# 08_SAMA7G54-DDR3.net
KiCad netlist of a schematic drawn in Altium Designer
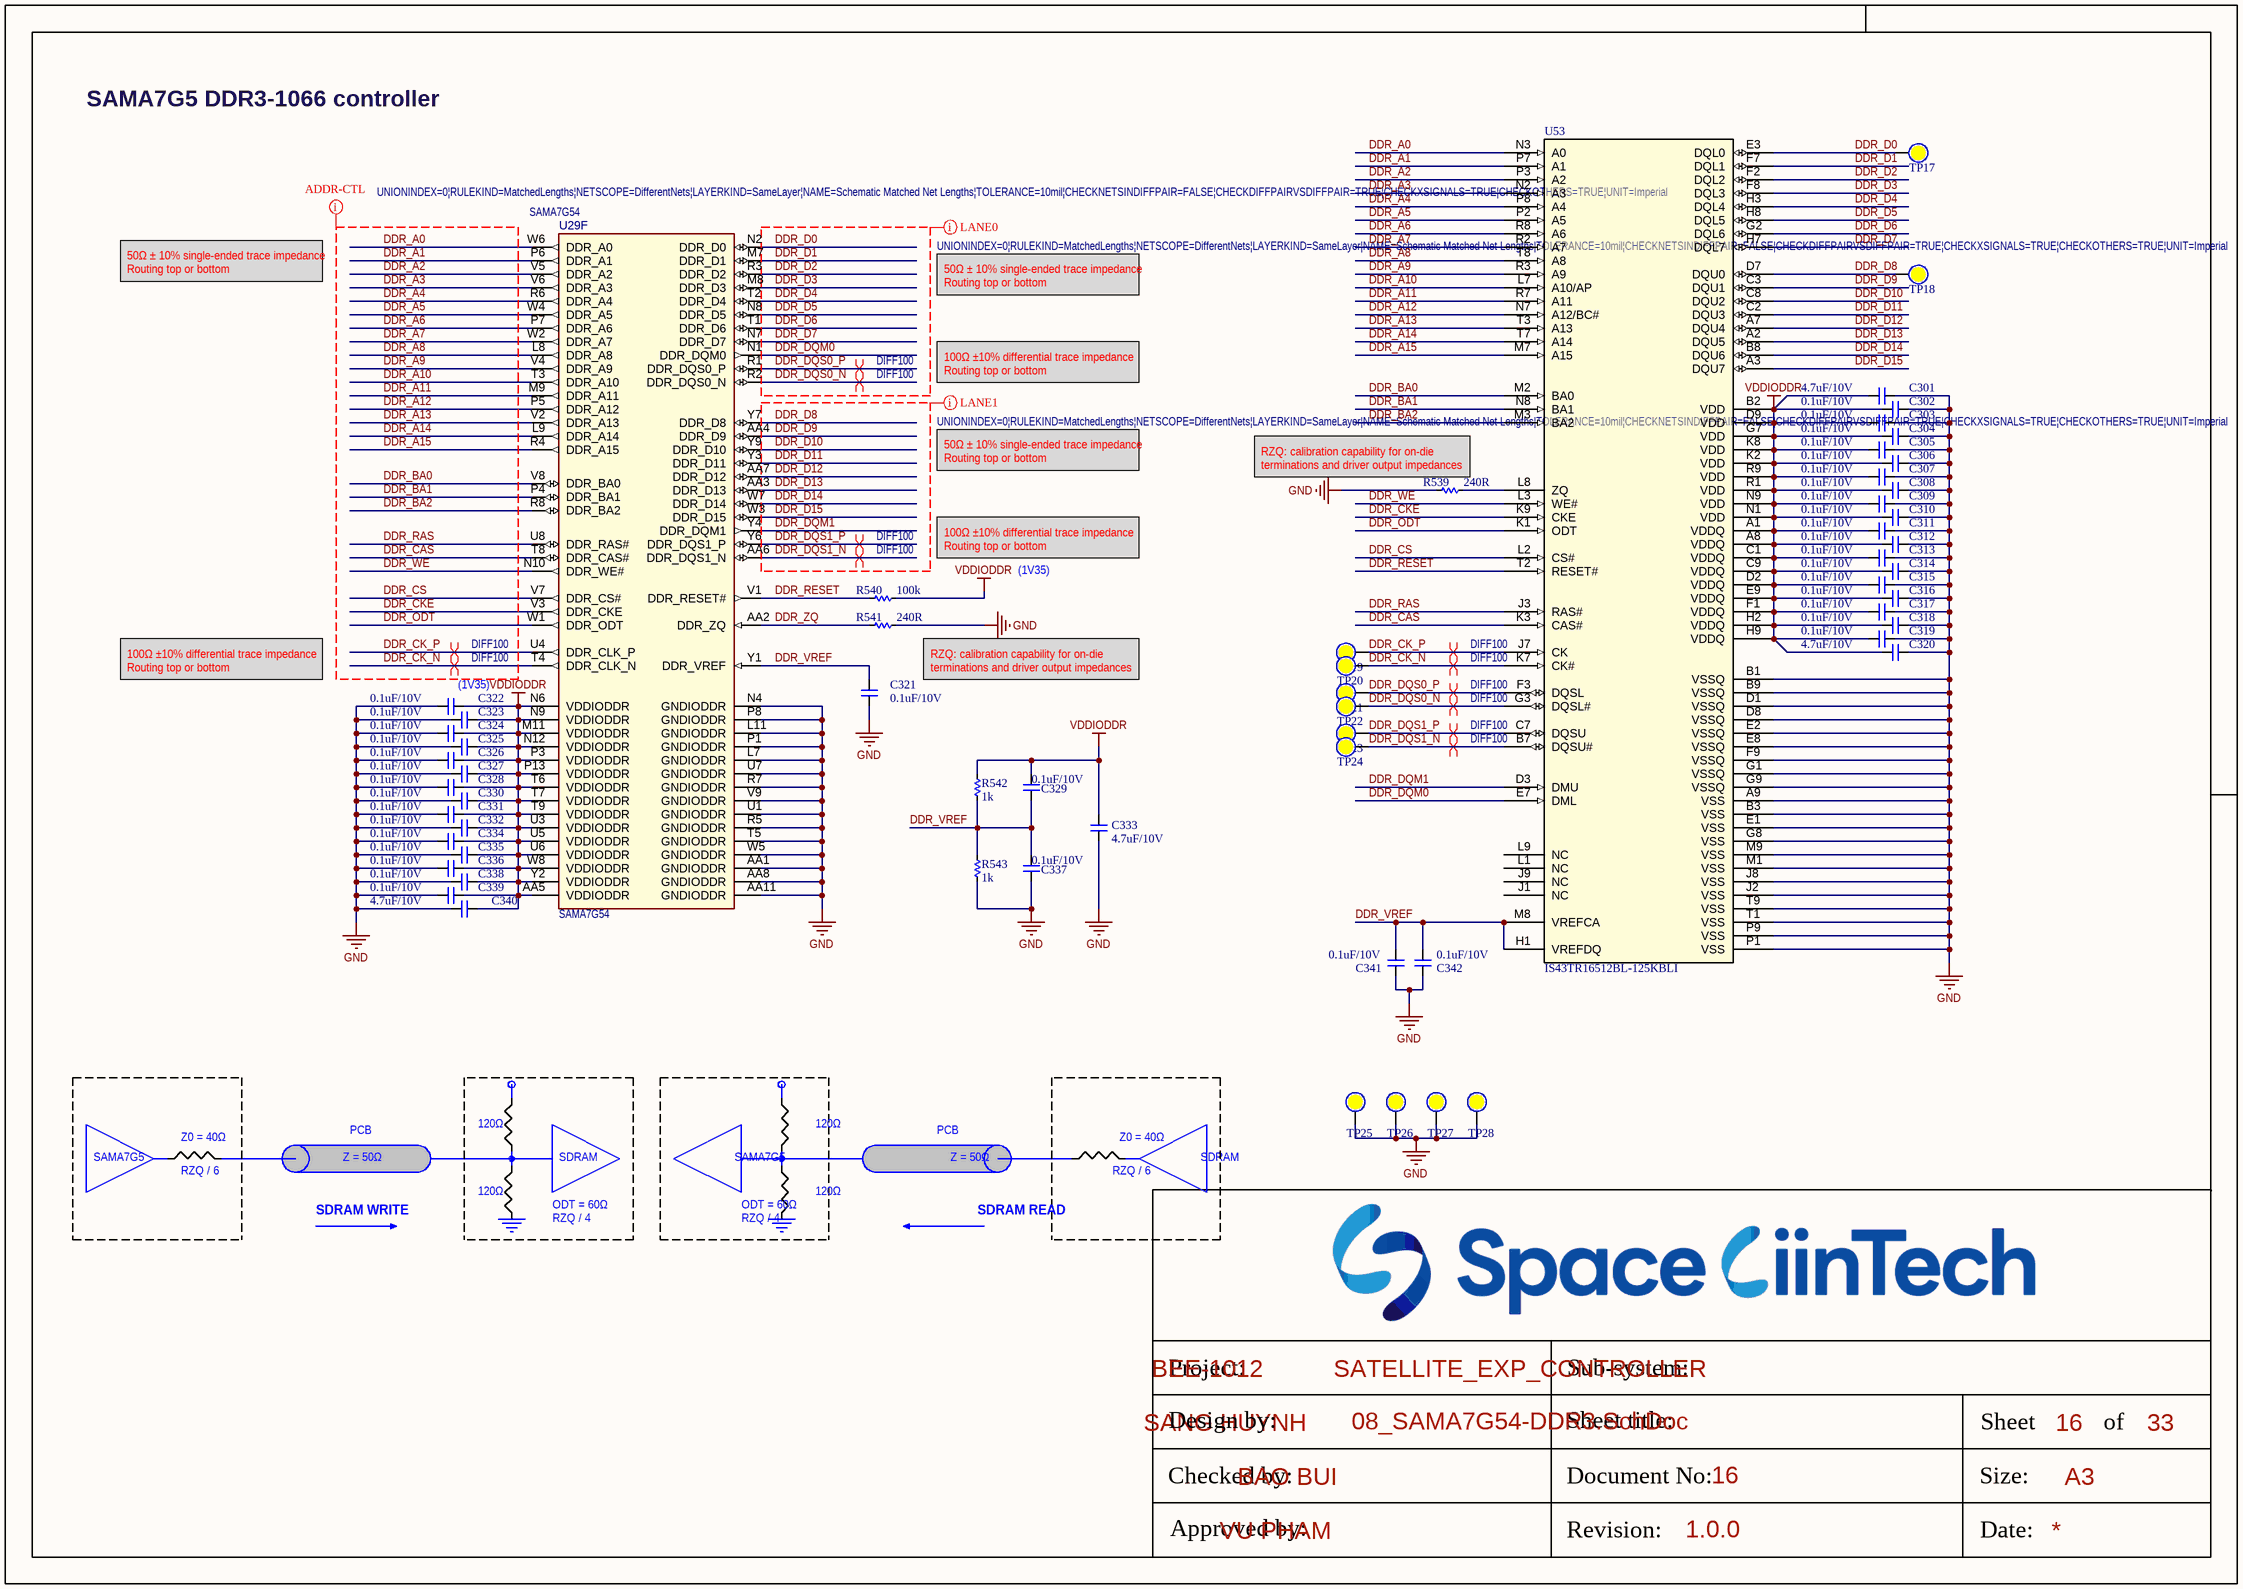
[diagram p0: 08_SAMA7G54-DDR3.SchDoc]

(export (version "E")
  (design (tool "Eeschema 10.0.6"))
  (components
    (comp (ref "C301")
      (value "4.7uF/10V")
      (footprint "CAP_C_1005X50_L")
      (description "CAP")
      (libsource (lib "LABLIB") (part "_CAP_C_2"))
    )
    (comp (ref "C302")
      (value "0.1uF/10V")
      (footprint "CAP_C_0603x30")
      (description "CAP")
      (libsource (lib "LABLIB") (part "_CAP_C_2"))
    )
    (comp (ref "C303")
      (value "0.1uF/10V")
      (footprint "CAP_C_0603x30")
      (description "CAP")
      (libsource (lib "LABLIB") (part "_CAP_C_2"))
    )
    (comp (ref "C304")
      (value "0.1uF/10V")
      (footprint "CAP_C_0603x30")
      (description "CAP")
      (libsource (lib "LABLIB") (part "_CAP_C_2"))
    )
    (comp (ref "C305")
      (value "0.1uF/10V")
      (footprint "CAP_C_0603x30")
      (description "CAP")
      (libsource (lib "LABLIB") (part "_CAP_C_2"))
    )
    (comp (ref "C306")
      (value "0.1uF/10V")
      (footprint "CAP_C_0603x30")
      (description "CAP")
      (libsource (lib "LABLIB") (part "_CAP_C_2"))
    )
    (comp (ref "C307")
      (value "0.1uF/10V")
      (footprint "CAP_C_0603x30")
      (description "CAP")
      (libsource (lib "LABLIB") (part "_CAP_C_2"))
    )
    (comp (ref "C308")
      (value "0.1uF/10V")
      (footprint "CAP_C_0603x30")
      (description "CAP")
      (libsource (lib "LABLIB") (part "_CAP_C_2"))
    )
    (comp (ref "C309")
      (value "0.1uF/10V")
      (footprint "CAP_C_0603x30")
      (description "CAP")
      (libsource (lib "LABLIB") (part "_CAP_C_2"))
    )
    (comp (ref "C310")
      (value "0.1uF/10V")
      (footprint "CAP_C_0603x30")
      (description "CAP")
      (libsource (lib "LABLIB") (part "_CAP_C_2"))
    )
    (comp (ref "C311")
      (value "0.1uF/10V")
      (footprint "CAP_C_0603x30")
      (description "CAP")
      (libsource (lib "LABLIB") (part "_CAP_C_2"))
    )
    (comp (ref "C312")
      (value "0.1uF/10V")
      (footprint "CAP_C_0603x30")
      (description "CAP")
      (libsource (lib "LABLIB") (part "_CAP_C_2"))
    )
    (comp (ref "C313")
      (value "0.1uF/10V")
      (footprint "CAP_C_0603x30")
      (description "CAP")
      (libsource (lib "LABLIB") (part "_CAP_C_2"))
    )
    (comp (ref "C314")
      (value "0.1uF/10V")
      (footprint "CAP_C_0603x30")
      (description "CAP")
      (libsource (lib "LABLIB") (part "_CAP_C_2"))
    )
    (comp (ref "C315")
      (value "0.1uF/10V")
      (footprint "CAP_C_0603x30")
      (description "CAP")
      (libsource (lib "LABLIB") (part "_CAP_C_2"))
    )
    (comp (ref "C316")
      (value "0.1uF/10V")
      (footprint "CAP_C_0603x30")
      (description "CAP")
      (libsource (lib "LABLIB") (part "_CAP_C_2"))
    )
    (comp (ref "C317")
      (value "0.1uF/10V")
      (footprint "CAP_C_0603x30")
      (description "CAP")
      (libsource (lib "LABLIB") (part "_CAP_C_2"))
    )
    (comp (ref "C318")
      (value "0.1uF/10V")
      (footprint "CAP_C_0603x30")
      (description "CAP")
      (libsource (lib "LABLIB") (part "_CAP_C_2"))
    )
    (comp (ref "C319")
      (value "0.1uF/10V")
      (footprint "CAP_C_0603x30")
      (description "CAP")
      (libsource (lib "LABLIB") (part "_CAP_C_2"))
    )
    (comp (ref "C320")
      (value "4.7uF/10V")
      (footprint "CAP_C_1005X50_L")
      (description "CAP")
      (libsource (lib "LABLIB") (part "_CAP_C_2"))
    )
    (comp (ref "C321")
      (value "0.1uF/10V")
      (footprint "CAP_C_0603x30")
      (description "CAP")
      (libsource (lib "LABLIB") (part "_CAP_C_2"))
    )
    (comp (ref "C322")
      (value "0.1uF/10V")
      (footprint "CAP_C_0603x30")
      (description "CAP")
      (libsource (lib "LABLIB") (part "_CAP_C_2"))
    )
    (comp (ref "C323")
      (value "0.1uF/10V")
      (footprint "CAP_C_0603x30")
      (description "CAP")
      (libsource (lib "LABLIB") (part "_CAP_C_2"))
    )
    (comp (ref "C324")
      (value "0.1uF/10V")
      (footprint "CAP_C_0603x30")
      (description "CAP")
      (libsource (lib "LABLIB") (part "_CAP_C_2"))
    )
    (comp (ref "C325")
      (value "0.1uF/10V")
      (footprint "CAP_C_0603x30")
      (description "CAP")
      (libsource (lib "LABLIB") (part "_CAP_C_2"))
    )
    (comp (ref "C326")
      (value "0.1uF/10V")
      (footprint "CAP_C_0603x30")
      (description "CAP")
      (libsource (lib "LABLIB") (part "_CAP_C_2"))
    )
    (comp (ref "C327")
      (value "0.1uF/10V")
      (footprint "CAP_C_0603x30")
      (description "CAP")
      (libsource (lib "LABLIB") (part "_CAP_C_2"))
    )
    (comp (ref "C328")
      (value "0.1uF/10V")
      (footprint "CAP_C_0603x30")
      (description "CAP")
      (libsource (lib "LABLIB") (part "_CAP_C_2"))
    )
    (comp (ref "C329")
      (value "0.1uF/10V")
      (footprint "CAP_C_0603x30")
      (description "CAP")
      (libsource (lib "LABLIB") (part "_CAP_C_2"))
    )
    (comp (ref "C330")
      (value "0.1uF/10V")
      (footprint "CAP_C_0603x30")
      (description "CAP")
      (libsource (lib "LABLIB") (part "_CAP_C_2"))
    )
    (comp (ref "C331")
      (value "0.1uF/10V")
      (footprint "CAP_C_0603x30")
      (description "CAP")
      (libsource (lib "LABLIB") (part "_CAP_C_2"))
    )
    (comp (ref "C332")
      (value "0.1uF/10V")
      (footprint "CAP_C_0603x30")
      (description "CAP")
      (libsource (lib "LABLIB") (part "_CAP_C_2"))
    )
    (comp (ref "C333")
      (value "4.7uF/10V")
      (footprint "CAP_C_1005X50_L")
      (description "CAP")
      (libsource (lib "LABLIB") (part "_CAP_C_2"))
    )
    (comp (ref "C334")
      (value "0.1uF/10V")
      (footprint "CAP_C_0603x30")
      (description "CAP")
      (libsource (lib "LABLIB") (part "_CAP_C_2"))
    )
    (comp (ref "C335")
      (value "0.1uF/10V")
      (footprint "CAP_C_0603x30")
      (description "CAP")
      (libsource (lib "LABLIB") (part "_CAP_C_2"))
    )
    (comp (ref "C336")
      (value "0.1uF/10V")
      (footprint "CAP_C_0603x30")
      (description "CAP")
      (libsource (lib "LABLIB") (part "_CAP_C_2"))
    )
    (comp (ref "C337")
      (value "0.1uF/10V")
      (footprint "CAP_C_0603x30")
      (description "CAP")
      (libsource (lib "LABLIB") (part "_CAP_C_2"))
    )
    (comp (ref "C338")
      (value "0.1uF/10V")
      (footprint "CAP_C_0603x30")
      (description "CAP")
      (libsource (lib "LABLIB") (part "_CAP_C_2"))
    )
    (comp (ref "C339")
      (value "0.1uF/10V")
      (footprint "CAP_C_0603x30")
      (description "CAP")
      (libsource (lib "LABLIB") (part "_CAP_C_2"))
    )
    (comp (ref "C340")
      (value "4.7uF/10V")
      (footprint "CAP_C_1005X50_L")
      (description "CAP")
      (libsource (lib "LABLIB") (part "_CAP_C_2"))
    )
    (comp (ref "C341")
      (value "0.1uF/10V")
      (footprint "CAP_C_0603x30")
      (description "CAP")
      (libsource (lib "LABLIB") (part "_CAP_C_2"))
    )
    (comp (ref "C342")
      (value "0.1uF/10V")
      (footprint "CAP_C_0603x30")
      (description "CAP")
      (libsource (lib "LABLIB") (part "_CAP_C_2"))
    )
    (comp (ref "R539")
      (value "240R")
      (footprint "RES_C_0603X30")
      (description "RES")
      (libsource (lib "LABLIB") (part "_RES_B_2"))
    )
    (comp (ref "R540")
      (value "100k")
      (footprint "RES_C_0603X30")
      (description "RES")
      (libsource (lib "LABLIB") (part "_RES_B_2"))
    )
    (comp (ref "R541")
      (value "240R")
      (footprint "RES_C_0603X30")
      (description "RES")
      (libsource (lib "LABLIB") (part "_RES_B_2"))
    )
    (comp (ref "R542")
      (value "1k")
      (footprint "RES_C_0603X30")
      (description "RES")
      (libsource (lib "LABLIB") (part "_RES_B_2"))
    )
    (comp (ref "R543")
      (value "1k")
      (footprint "RES_C_0603X30")
      (description "RES")
      (libsource (lib "LABLIB") (part "_RES_B_2"))
    )
    (comp (ref "TP17")
      (value "~")
      (footprint "TP_1mm_SMD")
      (description "Test Point")
      (libsource (lib "") (part "Test Point_2"))
    )
    (comp (ref "TP18")
      (value "~")
      (footprint "TP_1mm_SMD")
      (description "Test Point")
      (libsource (lib "") (part "Test Point_2"))
    )
    (comp (ref "TP19")
      (value "~")
      (footprint "TP_1mm_SMD")
      (description "Test Point")
      (libsource (lib "LABLIB") (part "Test Point"))
    )
    (comp (ref "TP20")
      (value "~")
      (footprint "TP_1mm_SMD")
      (description "Test Point")
      (libsource (lib "LABLIB") (part "Test Point"))
    )
    (comp (ref "TP21")
      (value "~")
      (footprint "TP_1mm_SMD")
      (description "Test Point")
      (libsource (lib "LABLIB") (part "Test Point"))
    )
    (comp (ref "TP22")
      (value "~")
      (footprint "TP_1mm_SMD")
      (description "Test Point")
      (libsource (lib "LABLIB") (part "Test Point"))
    )
    (comp (ref "TP23")
      (value "~")
      (footprint "TP_1mm_SMD")
      (description "Test Point")
      (libsource (lib "LABLIB") (part "Test Point"))
    )
    (comp (ref "TP24")
      (value "~")
      (footprint "TP_1mm_SMD")
      (description "Test Point")
      (libsource (lib "LABLIB") (part "Test Point"))
    )
    (comp (ref "TP25")
      (value "~")
      (footprint "TP_1mm_SMD")
      (description "Test Point")
      (libsource (lib "") (part "Test Point_1"))
    )
    (comp (ref "TP26")
      (value "~")
      (footprint "TP_1mm_SMD")
      (description "Test Point")
      (libsource (lib "") (part "Test Point_1"))
    )
    (comp (ref "TP27")
      (value "~")
      (footprint "TP_1mm_SMD")
      (description "Test Point")
      (libsource (lib "") (part "Test Point_1"))
    )
    (comp (ref "TP28")
      (value "~")
      (footprint "TP_1mm_SMD")
      (description "Test Point")
      (libsource (lib "") (part "Test Point_1"))
    )
    (comp (ref "U29")
      (value "SAMA7G54")
      (footprint "TFBGA-343_14x14 - 2.5mm")
      (description "SAMA7G54 MPU 1000MHz Cortex-A7 TFBGA-343")
      (fields (field (name "ALTIUM_VALUE") "SAMA7G54") (field (name "OWNER") "Ciprian Abramov"))
      (libsource (lib "LABLIB") (part "SAMA7G54"))
    )
    (comp (ref "U53")
      (value "IS43TR16512BL-125KBLI")
      (footprint "TWBGA96_ISI")
      (description "DDR3L")
      (fields (field (name "COPYRIGHT") "Copyright (C) 2025 Ultra Librarian. All rights reserved."))
      (libsource (lib "LABLIB") (part "IC_RAM_IS43TR16512BL-125KBLI"))
    )
  )
  (nets
    (net (code "1") (name "/DDR_A0") (class "Default")
      (node (ref "U29") (pin "W6") (pinfunction "DDR_A0_W6") (pintype "output"))
      (node (ref "U53") (pin "N3") (pinfunction "A0_N3") (pintype "input"))
    )
    (net (code "2") (name "/DDR_A1") (class "Default")
      (node (ref "U29") (pin "P6") (pinfunction "DDR_A1_P6") (pintype "output"))
      (node (ref "U53") (pin "P7") (pinfunction "A1_P7") (pintype "input"))
    )
    (net (code "3") (name "/DDR_A2") (class "Default")
      (node (ref "U29") (pin "V5") (pinfunction "DDR_A2_V5") (pintype "output"))
      (node (ref "U53") (pin "P3") (pinfunction "A2_P3") (pintype "input"))
    )
    (net (code "4") (name "/DDR_A3") (class "Default")
      (node (ref "U29") (pin "V6") (pinfunction "DDR_A3_V6") (pintype "output"))
      (node (ref "U53") (pin "N2") (pinfunction "A3_N2") (pintype "input"))
    )
    (net (code "5") (name "/DDR_A4") (class "Default")
      (node (ref "U29") (pin "R6") (pinfunction "DDR_A4_R6") (pintype "output"))
      (node (ref "U53") (pin "P8") (pinfunction "A4_P8") (pintype "input"))
    )
    (net (code "6") (name "/DDR_A5") (class "Default")
      (node (ref "U29") (pin "W4") (pinfunction "DDR_A5_W4") (pintype "output"))
      (node (ref "U53") (pin "P2") (pinfunction "A5_P2") (pintype "input"))
    )
    (net (code "7") (name "/DDR_A6") (class "Default")
      (node (ref "U29") (pin "P7") (pinfunction "DDR_A6_P7") (pintype "output"))
      (node (ref "U53") (pin "R8") (pinfunction "A6_R8") (pintype "input"))
    )
    (net (code "8") (name "/DDR_A7") (class "Default")
      (node (ref "U29") (pin "W2") (pinfunction "DDR_A7_W2") (pintype "output"))
      (node (ref "U53") (pin "R2") (pinfunction "A7_R2") (pintype "input"))
    )
    (net (code "9") (name "/DDR_A8") (class "Default")
      (node (ref "U29") (pin "L8") (pinfunction "DDR_A8_L8") (pintype "output"))
      (node (ref "U53") (pin "T8") (pinfunction "A8_T8") (pintype "input"))
    )
    (net (code "10") (name "/DDR_A9") (class "Default")
      (node (ref "U29") (pin "V4") (pinfunction "DDR_A9_V4") (pintype "output"))
      (node (ref "U53") (pin "R3") (pinfunction "A9_R3") (pintype "input"))
    )
    (net (code "11") (name "/DDR_A10") (class "Default")
      (node (ref "U29") (pin "T3") (pinfunction "DDR_A10_T3") (pintype "output"))
      (node (ref "U53") (pin "L7") (pinfunction "A10/AP_L7") (pintype "input"))
    )
    (net (code "12") (name "/DDR_A11") (class "Default")
      (node (ref "U29") (pin "M9") (pinfunction "DDR_A11_M9") (pintype "output"))
      (node (ref "U53") (pin "R7") (pinfunction "A11_R7") (pintype "input"))
    )
    (net (code "13") (name "/DDR_A12") (class "Default")
      (node (ref "U29") (pin "P5") (pinfunction "DDR_A12_P5") (pintype "output"))
      (node (ref "U53") (pin "N7") (pinfunction "A12/BC#_N7") (pintype "input"))
    )
    (net (code "14") (name "/DDR_A13") (class "Default")
      (node (ref "U29") (pin "V2") (pinfunction "DDR_A13_V2") (pintype "output"))
      (node (ref "U53") (pin "T3") (pinfunction "A13_T3") (pintype "input"))
    )
    (net (code "15") (name "/DDR_A14") (class "Default")
      (node (ref "U29") (pin "L9") (pinfunction "DDR_A14_L9") (pintype "output"))
      (node (ref "U53") (pin "T7") (pinfunction "A14_T7") (pintype "input"))
    )
    (net (code "16") (name "/DDR_A15") (class "Default")
      (node (ref "U29") (pin "R4") (pinfunction "DDR_A15_R4") (pintype "output"))
      (node (ref "U53") (pin "M7") (pinfunction "A15_M7") (pintype "input"))
    )
    (net (code "17") (name "/DDR_BA0") (class "Default")
      (node (ref "U29") (pin "V8") (pinfunction "DDR_BA0_V8") (pintype "bidirectional"))
      (node (ref "U53") (pin "M2") (pinfunction "BA0_M2") (pintype "input"))
    )
    (net (code "18") (name "/DDR_BA1") (class "Default")
      (node (ref "U29") (pin "P4") (pinfunction "DDR_BA1_P4") (pintype "bidirectional"))
      (node (ref "U53") (pin "N8") (pinfunction "BA1_N8") (pintype "input"))
    )
    (net (code "19") (name "/DDR_BA2") (class "Default")
      (node (ref "U29") (pin "R8") (pinfunction "DDR_BA2_R8") (pintype "bidirectional"))
      (node (ref "U53") (pin "M3") (pinfunction "BA2_M3") (pintype "input"))
    )
    (net (code "20") (name "/DDR_CAS") (class "Default")
      (node (ref "U29") (pin "T8") (pinfunction "DDR_CAS#_T8") (pintype "bidirectional"))
      (node (ref "U53") (pin "K3") (pinfunction "CAS#_K3") (pintype "input"))
    )
    (net (code "21") (name "/DDR_CKE") (class "Default")
      (node (ref "U29") (pin "V3") (pinfunction "DDR_CKE_V3") (pintype "output"))
      (node (ref "U53") (pin "K9") (pinfunction "CKE_K9") (pintype "input"))
    )
    (net (code "22") (name "/DDR_CK_N") (class "Default")
      (node (ref "TP20") (pin "0") (pinfunction "0_0") (pintype "passive"))
      (node (ref "U29") (pin "T4") (pinfunction "DDR_CLK_N_T4") (pintype "output"))
      (node (ref "U53") (pin "K7") (pinfunction "CK#_K7") (pintype "input"))
    )
    (net (code "23") (name "/DDR_CK_P") (class "Default")
      (node (ref "TP19") (pin "0") (pinfunction "0_0") (pintype "passive"))
      (node (ref "U29") (pin "U4") (pinfunction "DDR_CLK_P_U4") (pintype "output"))
      (node (ref "U53") (pin "J7") (pinfunction "CK_J7") (pintype "input"))
    )
    (net (code "24") (name "/DDR_CS") (class "Default")
      (node (ref "U29") (pin "V7") (pinfunction "DDR_CS#_V7") (pintype "output"))
      (node (ref "U53") (pin "L2") (pinfunction "CS#_L2") (pintype "input"))
    )
    (net (code "25") (name "/DDR_D0") (class "Default")
      (node (ref "TP17") (pin "0") (pinfunction "0_0") (pintype "passive"))
      (node (ref "U29") (pin "N2") (pinfunction "DDR_D0_N2") (pintype "bidirectional"))
      (node (ref "U53") (pin "E3") (pinfunction "DQL0_E3") (pintype "bidirectional"))
    )
    (net (code "26") (name "/DDR_D1") (class "Default")
      (node (ref "U29") (pin "M7") (pinfunction "DDR_D1_M7") (pintype "bidirectional"))
      (node (ref "U53") (pin "F7") (pinfunction "DQL1_F7") (pintype "bidirectional"))
    )
    (net (code "27") (name "/DDR_D2") (class "Default")
      (node (ref "U29") (pin "R3") (pinfunction "DDR_D2_R3") (pintype "bidirectional"))
      (node (ref "U53") (pin "F2") (pinfunction "DQL2_F2") (pintype "bidirectional"))
    )
    (net (code "28") (name "/DDR_D3") (class "Default")
      (node (ref "U29") (pin "M8") (pinfunction "DDR_D3_M8") (pintype "bidirectional"))
      (node (ref "U53") (pin "F8") (pinfunction "DQL3_F8") (pintype "bidirectional"))
    )
    (net (code "29") (name "/DDR_D4") (class "Default")
      (node (ref "U29") (pin "T2") (pinfunction "DDR_D4_T2") (pintype "bidirectional"))
      (node (ref "U53") (pin "H3") (pinfunction "DQL4_H3") (pintype "bidirectional"))
    )
    (net (code "30") (name "/DDR_D5") (class "Default")
      (node (ref "U29") (pin "N8") (pinfunction "DDR_D5_N8") (pintype "bidirectional"))
      (node (ref "U53") (pin "H8") (pinfunction "DQL5_H8") (pintype "bidirectional"))
    )
    (net (code "31") (name "/DDR_D6") (class "Default")
      (node (ref "U29") (pin "T1") (pinfunction "DDR_D6_T1") (pintype "bidirectional"))
      (node (ref "U53") (pin "G2") (pinfunction "DQL6_G2") (pintype "bidirectional"))
    )
    (net (code "32") (name "/DDR_D7") (class "Default")
      (node (ref "U29") (pin "N7") (pinfunction "DDR_D7_N7") (pintype "bidirectional"))
      (node (ref "U53") (pin "H7") (pinfunction "DQL7_H7") (pintype "bidirectional"))
    )
    (net (code "33") (name "/DDR_D8") (class "Default")
      (node (ref "TP18") (pin "0") (pinfunction "0_0") (pintype "passive"))
      (node (ref "U29") (pin "Y7") (pinfunction "DDR_D8_Y7") (pintype "bidirectional"))
      (node (ref "U53") (pin "D7") (pinfunction "DQU0_D7") (pintype "bidirectional"))
    )
    (net (code "34") (name "/DDR_D9") (class "Default")
      (node (ref "U29") (pin "AA4") (pinfunction "DDR_D9_AA4") (pintype "bidirectional"))
      (node (ref "U53") (pin "C3") (pinfunction "DQU1_C3") (pintype "bidirectional"))
    )
    (net (code "35") (name "/DDR_D10") (class "Default")
      (node (ref "U29") (pin "Y9") (pinfunction "DDR_D10_Y9") (pintype "bidirectional"))
      (node (ref "U53") (pin "C8") (pinfunction "DQU2_C8") (pintype "bidirectional"))
    )
    (net (code "36") (name "/DDR_D11") (class "Default")
      (node (ref "U29") (pin "Y3") (pinfunction "DDR_D11_Y3") (pintype "bidirectional"))
      (node (ref "U53") (pin "C2") (pinfunction "DQU3_C2") (pintype "bidirectional"))
    )
    (net (code "37") (name "/DDR_D12") (class "Default")
      (node (ref "U29") (pin "AA7") (pinfunction "DDR_D12_AA7") (pintype "bidirectional"))
      (node (ref "U53") (pin "A7") (pinfunction "DQU4_A7") (pintype "bidirectional"))
    )
    (net (code "38") (name "/DDR_D13") (class "Default")
      (node (ref "U29") (pin "AA3") (pinfunction "DDR_D13_AA3") (pintype "bidirectional"))
      (node (ref "U53") (pin "A2") (pinfunction "DQU5_A2") (pintype "bidirectional"))
    )
    (net (code "39") (name "/DDR_D14") (class "Default")
      (node (ref "U29") (pin "W7") (pinfunction "DDR_D14_W7") (pintype "bidirectional"))
      (node (ref "U53") (pin "B8") (pinfunction "DQU6_B8") (pintype "bidirectional"))
    )
    (net (code "40") (name "/DDR_D15") (class "Default")
      (node (ref "U29") (pin "W3") (pinfunction "DDR_D15_W3") (pintype "bidirectional"))
      (node (ref "U53") (pin "A3") (pinfunction "DQU7_A3") (pintype "bidirectional"))
    )
    (net (code "41") (name "/DDR_DQM0") (class "Default")
      (node (ref "U29") (pin "N1") (pinfunction "DDR_DQM0_N1") (pintype "output"))
      (node (ref "U53") (pin "E7") (pinfunction "DML_E7") (pintype "input"))
    )
    (net (code "42") (name "/DDR_DQM1") (class "Default")
      (node (ref "U29") (pin "Y4") (pinfunction "DDR_DQM1_Y4") (pintype "output"))
      (node (ref "U53") (pin "D3") (pinfunction "DMU_D3") (pintype "input"))
    )
    (net (code "43") (name "/DDR_DQS0_N") (class "Default")
      (node (ref "TP22") (pin "0") (pinfunction "0_0") (pintype "passive"))
      (node (ref "U29") (pin "R2") (pinfunction "DDR_DQS0_N_R2") (pintype "bidirectional"))
      (node (ref "U53") (pin "G3") (pinfunction "DQSL#_G3") (pintype "bidirectional"))
    )
    (net (code "44") (name "/DDR_DQS0_P") (class "Default")
      (node (ref "TP21") (pin "0") (pinfunction "0_0") (pintype "passive"))
      (node (ref "U29") (pin "R1") (pinfunction "DDR_DQS0_P_R1") (pintype "bidirectional"))
      (node (ref "U53") (pin "F3") (pinfunction "DQSL_F3") (pintype "bidirectional"))
    )
    (net (code "45") (name "/DDR_DQS1_N") (class "Default")
      (node (ref "TP24") (pin "0") (pinfunction "0_0") (pintype "passive"))
      (node (ref "U29") (pin "AA6") (pinfunction "DDR_DQS1_N_AA6") (pintype "bidirectional"))
      (node (ref "U53") (pin "B7") (pinfunction "DQSU#_B7") (pintype "bidirectional"))
    )
    (net (code "46") (name "/DDR_DQS1_P") (class "Default")
      (node (ref "TP23") (pin "0") (pinfunction "0_0") (pintype "passive"))
      (node (ref "U29") (pin "Y6") (pinfunction "DDR_DQS1_P_Y6") (pintype "bidirectional"))
      (node (ref "U53") (pin "C7") (pinfunction "DQSU_C7") (pintype "bidirectional"))
    )
    (net (code "47") (name "/DDR_ODT") (class "Default")
      (node (ref "U29") (pin "W1") (pinfunction "DDR_ODT_W1") (pintype "output"))
      (node (ref "U53") (pin "K1") (pinfunction "ODT_K1") (pintype "input"))
    )
    (net (code "48") (name "/DDR_RAS") (class "Default")
      (node (ref "U29") (pin "U8") (pinfunction "DDR_RAS#_U8") (pintype "bidirectional"))
      (node (ref "U53") (pin "J3") (pinfunction "RAS#_J3") (pintype "input"))
    )
    (net (code "49") (name "/DDR_RESET") (class "Default")
      (node (ref "R540") (pin "2") (pinfunction "2_2") (pintype "passive"))
      (node (ref "U29") (pin "V1") (pinfunction "DDR_RESET#_V1") (pintype "output"))
      (node (ref "U53") (pin "T2") (pinfunction "RESET#_T2") (pintype "input"))
    )
    (net (code "50") (name "/DDR_VREF") (class "Default")
      (node (ref "C321") (pin "1") (pinfunction "1_1") (pintype "passive"))
      (node (ref "C329") (pin "2") (pinfunction "2_2") (pintype "passive"))
      (node (ref "C337") (pin "1") (pinfunction "1_1") (pintype "passive"))
      (node (ref "C341") (pin "1") (pinfunction "1_1") (pintype "passive"))
      (node (ref "C342") (pin "1") (pinfunction "1_1") (pintype "passive"))
      (node (ref "R542") (pin "2") (pinfunction "2_2") (pintype "passive"))
      (node (ref "R543") (pin "1") (pinfunction "1_1") (pintype "passive"))
      (node (ref "U29") (pin "Y1") (pinfunction "DDR_VREF_Y1") (pintype "input"))
      (node (ref "U53") (pin "H1") (pinfunction "VREFDQ_H1") (pintype "power_in"))
      (node (ref "U53") (pin "M8") (pinfunction "VREFCA_M8") (pintype "power_in"))
    )
    (net (code "51") (name "/DDR_WE") (class "Default")
      (node (ref "U29") (pin "N10") (pinfunction "DDR_WE#_N10") (pintype "output"))
      (node (ref "U53") (pin "L3") (pinfunction "WE#_L3") (pintype "input"))
    )
    (net (code "52") (name "/DDR_ZQ") (class "Default")
      (node (ref "R541") (pin "2") (pinfunction "2_2") (pintype "passive"))
      (node (ref "U29") (pin "AA2") (pinfunction "DDR_ZQ_AA2") (pintype "input"))
    )
    (net (code "53") (name "GND") (class "Default")
      (node (ref "C301") (pin "1") (pinfunction "1_1") (pintype "passive"))
      (node (ref "C302") (pin "1") (pinfunction "1_1") (pintype "passive"))
      (node (ref "C303") (pin "1") (pinfunction "1_1") (pintype "passive"))
      (node (ref "C304") (pin "1") (pinfunction "1_1") (pintype "passive"))
      (node (ref "C305") (pin "1") (pinfunction "1_1") (pintype "passive"))
      (node (ref "C306") (pin "1") (pinfunction "1_1") (pintype "passive"))
      (node (ref "C307") (pin "1") (pinfunction "1_1") (pintype "passive"))
      (node (ref "C308") (pin "1") (pinfunction "1_1") (pintype "passive"))
      (node (ref "C309") (pin "1") (pinfunction "1_1") (pintype "passive"))
      (node (ref "C310") (pin "1") (pinfunction "1_1") (pintype "passive"))
      (node (ref "C311") (pin "1") (pinfunction "1_1") (pintype "passive"))
      (node (ref "C312") (pin "1") (pinfunction "1_1") (pintype "passive"))
      (node (ref "C313") (pin "1") (pinfunction "1_1") (pintype "passive"))
      (node (ref "C314") (pin "1") (pinfunction "1_1") (pintype "passive"))
      (node (ref "C315") (pin "1") (pinfunction "1_1") (pintype "passive"))
      (node (ref "C316") (pin "1") (pinfunction "1_1") (pintype "passive"))
      (node (ref "C317") (pin "1") (pinfunction "1_1") (pintype "passive"))
      (node (ref "C318") (pin "1") (pinfunction "1_1") (pintype "passive"))
      (node (ref "C319") (pin "1") (pinfunction "1_1") (pintype "passive"))
      (node (ref "C320") (pin "1") (pinfunction "1_1") (pintype "passive"))
      (node (ref "C321") (pin "2") (pinfunction "2_2") (pintype "passive"))
      (node (ref "C322") (pin "2") (pinfunction "2_2") (pintype "passive"))
      (node (ref "C323") (pin "2") (pinfunction "2_2") (pintype "passive"))
      (node (ref "C324") (pin "2") (pinfunction "2_2") (pintype "passive"))
      (node (ref "C325") (pin "2") (pinfunction "2_2") (pintype "passive"))
      (node (ref "C326") (pin "2") (pinfunction "2_2") (pintype "passive"))
      (node (ref "C327") (pin "2") (pinfunction "2_2") (pintype "passive"))
      (node (ref "C328") (pin "2") (pinfunction "2_2") (pintype "passive"))
      (node (ref "C330") (pin "2") (pinfunction "2_2") (pintype "passive"))
      (node (ref "C331") (pin "2") (pinfunction "2_2") (pintype "passive"))
      (node (ref "C332") (pin "2") (pinfunction "2_2") (pintype "passive"))
      (node (ref "C333") (pin "2") (pinfunction "2_2") (pintype "passive"))
      (node (ref "C334") (pin "2") (pinfunction "2_2") (pintype "passive"))
      (node (ref "C335") (pin "2") (pinfunction "2_2") (pintype "passive"))
      (node (ref "C336") (pin "2") (pinfunction "2_2") (pintype "passive"))
      (node (ref "C337") (pin "2") (pinfunction "2_2") (pintype "passive"))
      (node (ref "C338") (pin "2") (pinfunction "2_2") (pintype "passive"))
      (node (ref "C339") (pin "2") (pinfunction "2_2") (pintype "passive"))
      (node (ref "C340") (pin "2") (pinfunction "2_2") (pintype "passive"))
      (node (ref "C341") (pin "2") (pinfunction "2_2") (pintype "passive"))
      (node (ref "C342") (pin "2") (pinfunction "2_2") (pintype "passive"))
      (node (ref "R539") (pin "2") (pinfunction "2_2") (pintype "passive"))
      (node (ref "R541") (pin "1") (pinfunction "1_1") (pintype "passive"))
      (node (ref "R543") (pin "2") (pinfunction "2_2") (pintype "passive"))
      (node (ref "TP25") (pin "0") (pinfunction "0_0") (pintype "passive"))
      (node (ref "TP26") (pin "0") (pinfunction "0_0") (pintype "passive"))
      (node (ref "TP27") (pin "0") (pinfunction "0_0") (pintype "passive"))
      (node (ref "TP28") (pin "0") (pinfunction "0_0") (pintype "passive"))
      (node (ref "U29") (pin "AA1") (pinfunction "GNDIODDR_AA1") (pintype "power_in"))
      (node (ref "U29") (pin "AA11") (pinfunction "GNDIODDR_AA11") (pintype "power_in"))
      (node (ref "U29") (pin "AA8") (pinfunction "GNDIODDR_AA8") (pintype "power_in"))
      (node (ref "U29") (pin "L11") (pinfunction "GNDIODDR_L11") (pintype "power_in"))
      (node (ref "U29") (pin "L7") (pinfunction "GNDIODDR_L7") (pintype "power_in"))
      (node (ref "U29") (pin "N4") (pinfunction "GNDIODDR_N4") (pintype "power_in"))
      (node (ref "U29") (pin "P1") (pinfunction "GNDIODDR_P1") (pintype "power_in"))
      (node (ref "U29") (pin "P8") (pinfunction "GNDIODDR_P8") (pintype "power_in"))
      (node (ref "U29") (pin "R5") (pinfunction "GNDIODDR_R5") (pintype "power_in"))
      (node (ref "U29") (pin "R7") (pinfunction "GNDIODDR_R7") (pintype "power_in"))
      (node (ref "U29") (pin "T5") (pinfunction "GNDIODDR_T5") (pintype "power_in"))
      (node (ref "U29") (pin "U1") (pinfunction "GNDIODDR_U1") (pintype "power_in"))
      (node (ref "U29") (pin "U7") (pinfunction "GNDIODDR_U7") (pintype "power_in"))
      (node (ref "U29") (pin "V9") (pinfunction "GNDIODDR_V9") (pintype "power_in"))
      (node (ref "U29") (pin "W5") (pinfunction "GNDIODDR_W5") (pintype "power_in"))
      (node (ref "U53") (pin "A9") (pinfunction "VSS_A9") (pintype "power_in"))
      (node (ref "U53") (pin "B1") (pinfunction "VSSQ_B1") (pintype "power_in"))
      (node (ref "U53") (pin "B3") (pinfunction "VSS_B3") (pintype "power_in"))
      (node (ref "U53") (pin "B9") (pinfunction "VSSQ_B9") (pintype "power_in"))
      (node (ref "U53") (pin "D1") (pinfunction "VSSQ_D1") (pintype "power_in"))
      (node (ref "U53") (pin "D8") (pinfunction "VSSQ_D8") (pintype "power_in"))
      (node (ref "U53") (pin "E1") (pinfunction "VSS_E1") (pintype "power_in"))
      (node (ref "U53") (pin "E2") (pinfunction "VSSQ_E2") (pintype "power_in"))
      (node (ref "U53") (pin "E8") (pinfunction "VSSQ_E8") (pintype "power_in"))
      (node (ref "U53") (pin "F9") (pinfunction "VSSQ_F9") (pintype "power_in"))
      (node (ref "U53") (pin "G1") (pinfunction "VSSQ_G1") (pintype "power_in"))
      (node (ref "U53") (pin "G8") (pinfunction "VSS_G8") (pintype "power_in"))
      (node (ref "U53") (pin "G9") (pinfunction "VSSQ_G9") (pintype "power_in"))
      (node (ref "U53") (pin "J2") (pinfunction "VSS_J2") (pintype "power_in"))
      (node (ref "U53") (pin "J8") (pinfunction "VSS_J8") (pintype "power_in"))
      (node (ref "U53") (pin "M1") (pinfunction "VSS_M1") (pintype "power_in"))
      (node (ref "U53") (pin "M9") (pinfunction "VSS_M9") (pintype "power_in"))
      (node (ref "U53") (pin "P1") (pinfunction "VSS_P1") (pintype "power_in"))
      (node (ref "U53") (pin "P9") (pinfunction "VSS_P9") (pintype "power_in"))
      (node (ref "U53") (pin "T1") (pinfunction "VSS_T1") (pintype "power_in"))
      (node (ref "U53") (pin "T9") (pinfunction "VSS_T9") (pintype "power_in"))
    )
    (net (code "54") (name "Net-(U53-ZQ)") (class "Default")
      (node (ref "R539") (pin "1") (pinfunction "1_1") (pintype "passive"))
      (node (ref "U53") (pin "L8") (pinfunction "ZQ_L8") (pintype "power_in"))
    )
    (net (code "55") (name "VDDIODDR") (class "Default")
      (node (ref "C301") (pin "2") (pinfunction "2_2") (pintype "passive"))
      (node (ref "C302") (pin "2") (pinfunction "2_2") (pintype "passive"))
      (node (ref "C303") (pin "2") (pinfunction "2_2") (pintype "passive"))
      (node (ref "C304") (pin "2") (pinfunction "2_2") (pintype "passive"))
      (node (ref "C305") (pin "2") (pinfunction "2_2") (pintype "passive"))
      (node (ref "C306") (pin "2") (pinfunction "2_2") (pintype "passive"))
      (node (ref "C307") (pin "2") (pinfunction "2_2") (pintype "passive"))
      (node (ref "C308") (pin "2") (pinfunction "2_2") (pintype "passive"))
      (node (ref "C309") (pin "2") (pinfunction "2_2") (pintype "passive"))
      (node (ref "C310") (pin "2") (pinfunction "2_2") (pintype "passive"))
      (node (ref "C311") (pin "2") (pinfunction "2_2") (pintype "passive"))
      (node (ref "C312") (pin "2") (pinfunction "2_2") (pintype "passive"))
      (node (ref "C313") (pin "2") (pinfunction "2_2") (pintype "passive"))
      (node (ref "C314") (pin "2") (pinfunction "2_2") (pintype "passive"))
      (node (ref "C315") (pin "2") (pinfunction "2_2") (pintype "passive"))
      (node (ref "C316") (pin "2") (pinfunction "2_2") (pintype "passive"))
      (node (ref "C317") (pin "2") (pinfunction "2_2") (pintype "passive"))
      (node (ref "C318") (pin "2") (pinfunction "2_2") (pintype "passive"))
      (node (ref "C319") (pin "2") (pinfunction "2_2") (pintype "passive"))
      (node (ref "C320") (pin "2") (pinfunction "2_2") (pintype "passive"))
      (node (ref "C322") (pin "1") (pinfunction "1_1") (pintype "passive"))
      (node (ref "C323") (pin "1") (pinfunction "1_1") (pintype "passive"))
      (node (ref "C324") (pin "1") (pinfunction "1_1") (pintype "passive"))
      (node (ref "C325") (pin "1") (pinfunction "1_1") (pintype "passive"))
      (node (ref "C326") (pin "1") (pinfunction "1_1") (pintype "passive"))
      (node (ref "C327") (pin "1") (pinfunction "1_1") (pintype "passive"))
      (node (ref "C328") (pin "1") (pinfunction "1_1") (pintype "passive"))
      (node (ref "C329") (pin "1") (pinfunction "1_1") (pintype "passive"))
      (node (ref "C330") (pin "1") (pinfunction "1_1") (pintype "passive"))
      (node (ref "C331") (pin "1") (pinfunction "1_1") (pintype "passive"))
      (node (ref "C332") (pin "1") (pinfunction "1_1") (pintype "passive"))
      (node (ref "C333") (pin "1") (pinfunction "1_1") (pintype "passive"))
      (node (ref "C334") (pin "1") (pinfunction "1_1") (pintype "passive"))
      (node (ref "C335") (pin "1") (pinfunction "1_1") (pintype "passive"))
      (node (ref "C336") (pin "1") (pinfunction "1_1") (pintype "passive"))
      (node (ref "C338") (pin "1") (pinfunction "1_1") (pintype "passive"))
      (node (ref "C339") (pin "1") (pinfunction "1_1") (pintype "passive"))
      (node (ref "C340") (pin "1") (pinfunction "1_1") (pintype "passive"))
      (node (ref "R540") (pin "1") (pinfunction "1_1") (pintype "passive"))
      (node (ref "R542") (pin "1") (pinfunction "1_1") (pintype "passive"))
      (node (ref "U29") (pin "AA5") (pinfunction "VDDIODDR_AA5") (pintype "power_in"))
      (node (ref "U29") (pin "M11") (pinfunction "VDDIODDR_M11") (pintype "power_in"))
      (node (ref "U29") (pin "N12") (pinfunction "VDDIODDR_N12") (pintype "power_in"))
      (node (ref "U29") (pin "N6") (pinfunction "VDDIODDR_N6") (pintype "power_in"))
      (node (ref "U29") (pin "N9") (pinfunction "VDDIODDR_N9") (pintype "power_in"))
      (node (ref "U29") (pin "P13") (pinfunction "VDDIODDR_P13") (pintype "power_in"))
      (node (ref "U29") (pin "P3") (pinfunction "VDDIODDR_P3") (pintype "power_in"))
      (node (ref "U29") (pin "T6") (pinfunction "VDDIODDR_T6") (pintype "power_in"))
      (node (ref "U29") (pin "T7") (pinfunction "VDDIODDR_T7") (pintype "power_in"))
      (node (ref "U29") (pin "T9") (pinfunction "VDDIODDR_T9") (pintype "power_in"))
      (node (ref "U29") (pin "U3") (pinfunction "VDDIODDR_U3") (pintype "power_in"))
      (node (ref "U29") (pin "U5") (pinfunction "VDDIODDR_U5") (pintype "power_in"))
      (node (ref "U29") (pin "U6") (pinfunction "VDDIODDR_U6") (pintype "power_in"))
      (node (ref "U29") (pin "W8") (pinfunction "VDDIODDR_W8") (pintype "power_in"))
      (node (ref "U29") (pin "Y2") (pinfunction "VDDIODDR_Y2") (pintype "power_in"))
      (node (ref "U53") (pin "A1") (pinfunction "VDDQ_A1") (pintype "power_in"))
      (node (ref "U53") (pin "A8") (pinfunction "VDDQ_A8") (pintype "power_in"))
      (node (ref "U53") (pin "B2") (pinfunction "VDD_B2") (pintype "power_in"))
      (node (ref "U53") (pin "C1") (pinfunction "VDDQ_C1") (pintype "power_in"))
      (node (ref "U53") (pin "C9") (pinfunction "VDDQ_C9") (pintype "power_in"))
      (node (ref "U53") (pin "D2") (pinfunction "VDDQ_D2") (pintype "power_in"))
      (node (ref "U53") (pin "D9") (pinfunction "VDD_D9") (pintype "power_in"))
      (node (ref "U53") (pin "E9") (pinfunction "VDDQ_E9") (pintype "power_in"))
      (node (ref "U53") (pin "F1") (pinfunction "VDDQ_F1") (pintype "power_in"))
      (node (ref "U53") (pin "G7") (pinfunction "VDD_G7") (pintype "power_in"))
      (node (ref "U53") (pin "H2") (pinfunction "VDDQ_H2") (pintype "power_in"))
      (node (ref "U53") (pin "H9") (pinfunction "VDDQ_H9") (pintype "power_in"))
      (node (ref "U53") (pin "K2") (pinfunction "VDD_K2") (pintype "power_in"))
      (node (ref "U53") (pin "K8") (pinfunction "VDD_K8") (pintype "power_in"))
      (node (ref "U53") (pin "N1") (pinfunction "VDD_N1") (pintype "power_in"))
      (node (ref "U53") (pin "N9") (pinfunction "VDD_N9") (pintype "power_in"))
      (node (ref "U53") (pin "R1") (pinfunction "VDD_R1") (pintype "power_in"))
      (node (ref "U53") (pin "R9") (pinfunction "VDD_R9") (pintype "power_in"))
    )
    (net (code "56") (name "unconnected-(U53-NC-PadJ1)") (class "Default")
      (node (ref "U53") (pin "J1") (pinfunction "NC_J1") (pintype "passive"))
    )
    (net (code "57") (name "unconnected-(U53-NC-PadJ9)") (class "Default")
      (node (ref "U53") (pin "J9") (pinfunction "NC_J9") (pintype "passive"))
    )
    (net (code "58") (name "unconnected-(U53-NC-PadL1)") (class "Default")
      (node (ref "U53") (pin "L1") (pinfunction "NC_L1") (pintype "passive"))
    )
    (net (code "59") (name "unconnected-(U53-NC-PadL9)") (class "Default")
      (node (ref "U53") (pin "L9") (pinfunction "NC_L9") (pintype "passive"))
    )
  )
)
